# 232.net
KiCad netlist of a schematic drawn in Altium Designer
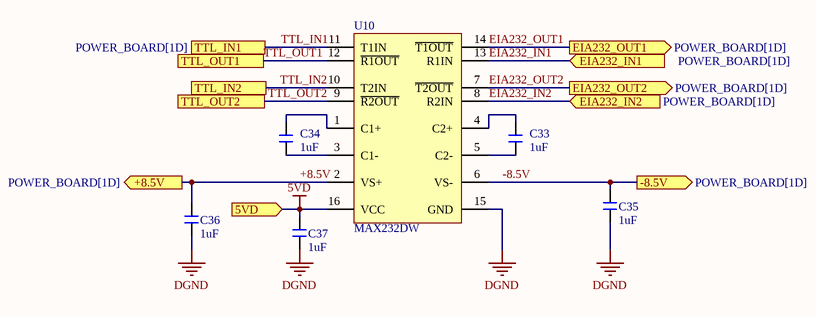
[diagram p0: 232收发器.SchDoc]

(export (version "E")
  (design (tool "Eeschema 10.0.6"))
  (components
    (comp (ref "C33")
      (value "1uF")
      (footprint "C 0805_L")
      (description "贴片电容")
      (libsource (lib "0.1 - 电阻-电容-电感") (part "C"))
    )
    (comp (ref "C34")
      (value "1uF")
      (footprint "C 0805_L")
      (description "贴片电容")
      (libsource (lib "0.1 - 电阻-电容-电感") (part "C"))
    )
    (comp (ref "C35")
      (value "1uF")
      (footprint "C 0805_L")
      (description "贴片电容")
      (libsource (lib "0.1 - 电阻-电容-电感") (part "C"))
    )
    (comp (ref "C36")
      (value "1uF")
      (footprint "C 0805_L")
      (description "贴片电容")
      (libsource (lib "0.1 - 电阻-电容-电感") (part "C"))
    )
    (comp (ref "C37")
      (value "1uF")
      (footprint "C 0805_L")
      (description "贴片电容")
      (libsource (lib "0.1 - 电阻-电容-电感") (part "C"))
    )
    (comp (ref "U10")
      (value "MAX232DW")
      (footprint "DW0016A_N")
      (description "Dual EIA-232 Driver / Receiver, 0 to 70 degC, 16-Pin SOIC (DW), Green (RoHS & no Sb/Br)")
      (libsource (lib "Components - 25.10.23 - 19.05") (part "CMP-0299-00141-2"))
    )
  )
  (nets
    (net (code "1") (name "/+8.5V") (class "Default")
      (node (ref "C36") (pin "2") (pinfunction "2_2") (pintype "passive"))
      (node (ref "U10") (pin "2") (pinfunction "VS+_2") (pintype "passive"))
    )
    (net (code "2") (name "/-8.5V") (class "Default")
      (node (ref "C35") (pin "2") (pinfunction "2_2") (pintype "passive"))
      (node (ref "U10") (pin "6") (pinfunction "VS-_6") (pintype "passive"))
    )
    (net (code "3") (name "/EIA232_IN1") (class "Default")
      (node (ref "U10") (pin "13") (pinfunction "R1IN_13") (pintype "passive"))
    )
    (net (code "4") (name "/EIA232_IN2") (class "Default")
      (node (ref "U10") (pin "8") (pinfunction "R2IN_8") (pintype "passive"))
    )
    (net (code "5") (name "/EIA232_OUT1") (class "Default")
      (node (ref "U10") (pin "14") (pinfunction "~{T1OUT}_14") (pintype "passive"))
    )
    (net (code "6") (name "/EIA232_OUT2") (class "Default")
      (node (ref "U10") (pin "7") (pinfunction "~{T2OUT}_7") (pintype "passive"))
    )
    (net (code "7") (name "/TTL_IN1") (class "Default")
      (node (ref "U10") (pin "11") (pinfunction "T1IN_11") (pintype "passive"))
    )
    (net (code "8") (name "/TTL_IN2") (class "Default")
      (node (ref "U10") (pin "10") (pinfunction "T2IN_10") (pintype "passive"))
    )
    (net (code "9") (name "/TTL_OUT1") (class "Default")
      (node (ref "U10") (pin "12") (pinfunction "~{R1OUT}_12") (pintype "passive"))
    )
    (net (code "10") (name "/TTL_OUT2") (class "Default")
      (node (ref "U10") (pin "9") (pinfunction "~{R2OUT}_9") (pintype "passive"))
    )
    (net (code "11") (name "5VD") (class "Default")
      (node (ref "C37") (pin "2") (pinfunction "2_2") (pintype "passive"))
      (node (ref "U10") (pin "16") (pinfunction "VCC_16") (pintype "passive"))
    )
    (net (code "12") (name "DGND") (class "Default")
      (node (ref "C35") (pin "1") (pinfunction "1_1") (pintype "passive"))
      (node (ref "C36") (pin "1") (pinfunction "1_1") (pintype "passive"))
      (node (ref "C37") (pin "1") (pinfunction "1_1") (pintype "passive"))
      (node (ref "U10") (pin "15") (pinfunction "GND_15") (pintype "power_in"))
    )
    (net (code "13") (name "Net-(U10-C1+)") (class "Default")
      (node (ref "C34") (pin "2") (pinfunction "2_2") (pintype "passive"))
      (node (ref "U10") (pin "1") (pinfunction "C1+_1") (pintype "passive"))
    )
    (net (code "14") (name "Net-(U10-C1-)") (class "Default")
      (node (ref "C34") (pin "1") (pinfunction "1_1") (pintype "passive"))
      (node (ref "U10") (pin "3") (pinfunction "C1-_3") (pintype "passive"))
    )
    (net (code "15") (name "Net-(U10-C2+)") (class "Default")
      (node (ref "C33") (pin "2") (pinfunction "2_2") (pintype "passive"))
      (node (ref "U10") (pin "4") (pinfunction "C2+_4") (pintype "passive"))
    )
    (net (code "16") (name "Net-(U10-C2-)") (class "Default")
      (node (ref "C33") (pin "1") (pinfunction "1_1") (pintype "passive"))
      (node (ref "U10") (pin "5") (pinfunction "C2-_5") (pintype "passive"))
    )
  )
)
